# WattMeter_v2.net
KiCad netlist of a schematic drawn in EAGLE
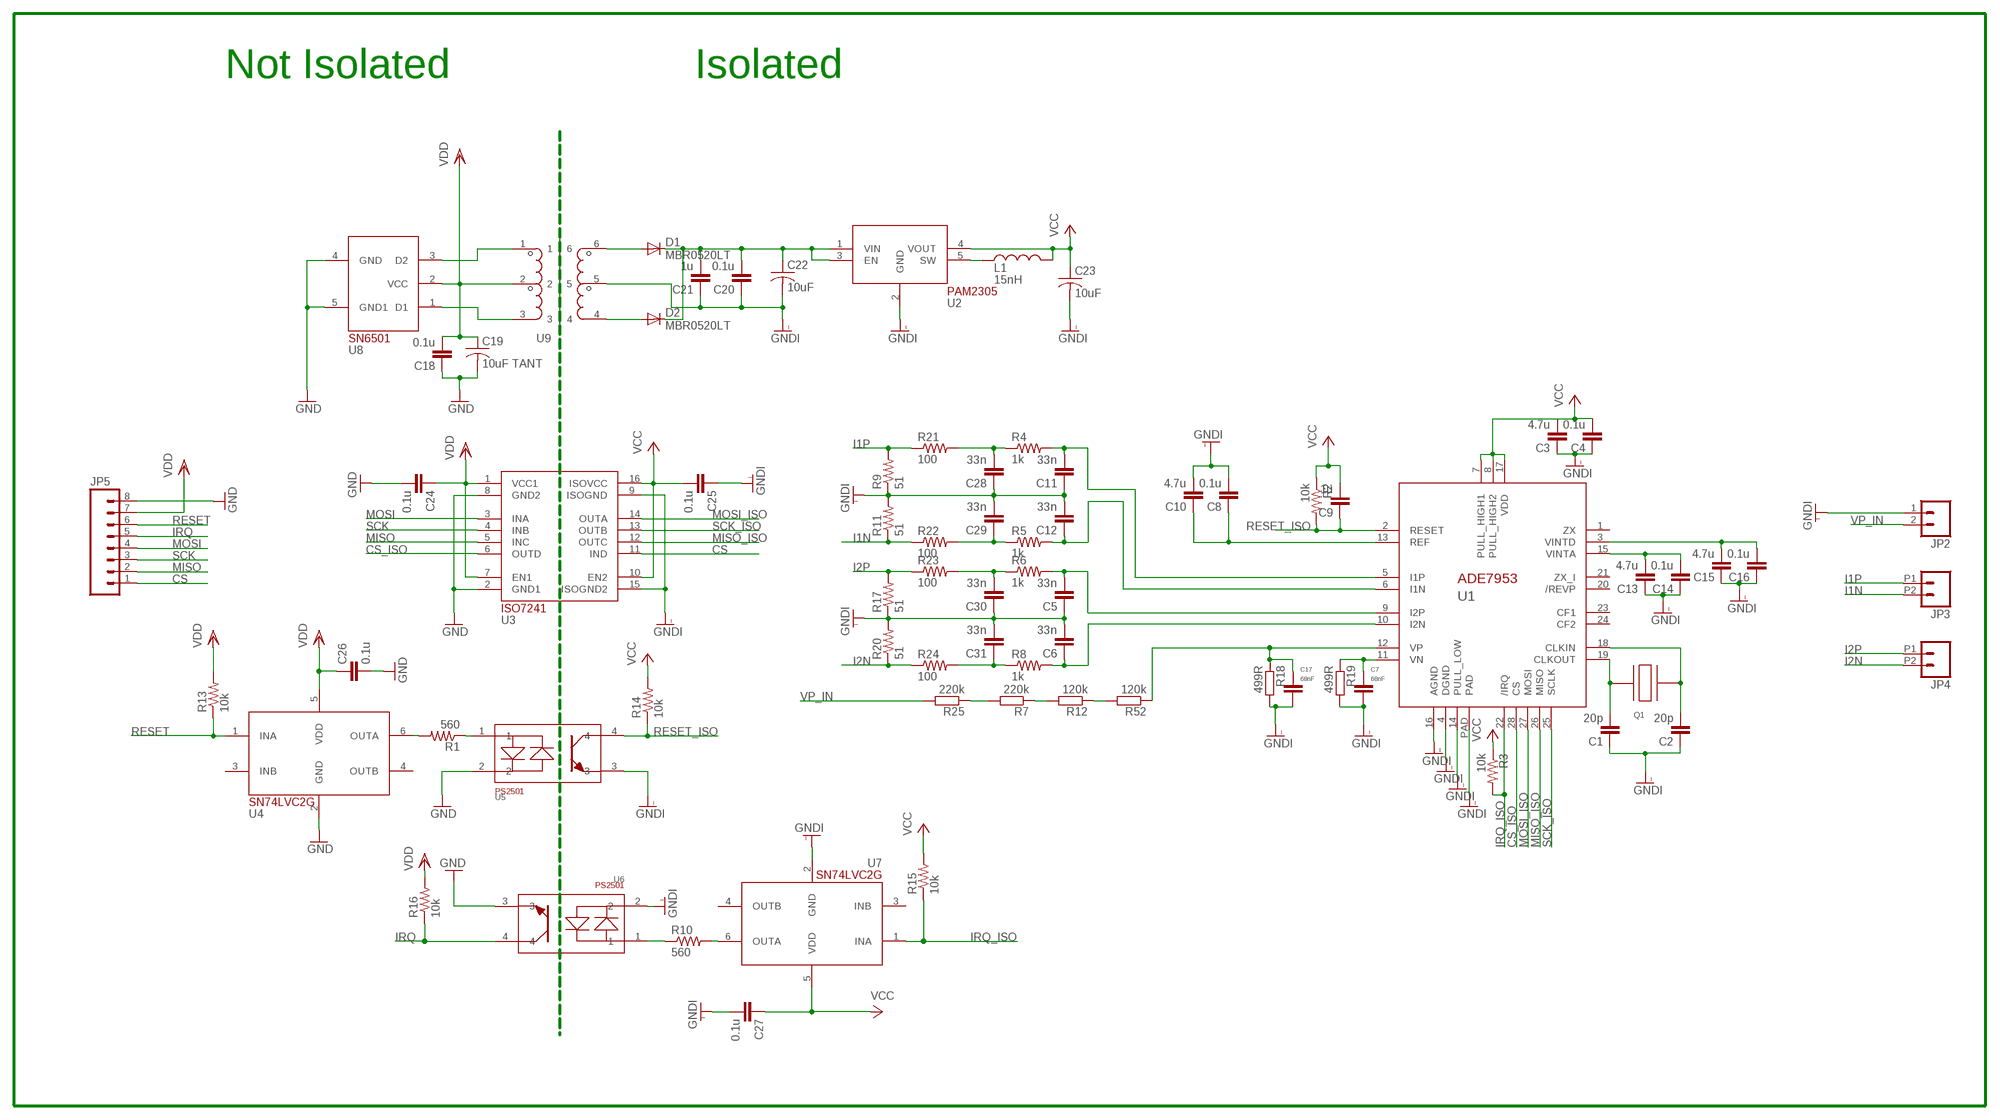
[diagram p0: schematic, sheet 1]

(export (version "E")
  (design (tool "Eeschema 10.0.6"))
  (components
    (comp (ref "C1")
      (value "20p")
      (footprint "eagle-import:0402-CAP")
      (libsource (lib "eagle-import") (part "0402-CAP"))
    )
    (comp (ref "C2")
      (value "20p")
      (footprint "eagle-import:0402-CAP")
      (libsource (lib "eagle-import") (part "0402-CAP"))
    )
    (comp (ref "C3")
      (value "4.7u")
      (footprint "eagle-import:0402-CAP")
      (libsource (lib "eagle-import") (part "0402-CAP"))
    )
    (comp (ref "C4")
      (value "0.1u")
      (footprint "eagle-import:0402-CAP")
      (libsource (lib "eagle-import") (part "0402-CAP"))
    )
    (comp (ref "C5")
      (value "33n")
      (footprint "eagle-import:0402-CAP")
      (libsource (lib "eagle-import") (part "0402-CAP"))
    )
    (comp (ref "C6")
      (value "33n")
      (footprint "eagle-import:0402-CAP")
      (libsource (lib "eagle-import") (part "0402-CAP"))
    )
    (comp (ref "C7")
      (value "68nF")
      (footprint "eagle-import:C0805K")
      (libsource (lib "eagle-import") (part "C-EUC0805K"))
    )
    (comp (ref "C8")
      (value "0.1u")
      (footprint "eagle-import:0402-CAP")
      (libsource (lib "eagle-import") (part "0402-CAP"))
    )
    (comp (ref "C9")
      (value "1u")
      (footprint "eagle-import:0402-CAP")
      (libsource (lib "eagle-import") (part "0402-CAP"))
    )
    (comp (ref "C10")
      (value "4.7u")
      (footprint "eagle-import:0402-CAP")
      (libsource (lib "eagle-import") (part "0402-CAP"))
    )
    (comp (ref "C11")
      (value "33n")
      (footprint "eagle-import:0402-CAP")
      (libsource (lib "eagle-import") (part "0402-CAP"))
    )
    (comp (ref "C12")
      (value "33n")
      (footprint "eagle-import:0402-CAP")
      (libsource (lib "eagle-import") (part "0402-CAP"))
    )
    (comp (ref "C13")
      (value "4.7u")
      (footprint "eagle-import:0402-CAP")
      (libsource (lib "eagle-import") (part "0402-CAP"))
    )
    (comp (ref "C14")
      (value "0.1u")
      (footprint "eagle-import:0402-CAP")
      (libsource (lib "eagle-import") (part "0402-CAP"))
    )
    (comp (ref "C15")
      (value "4.7u")
      (footprint "eagle-import:0402-CAP")
      (libsource (lib "eagle-import") (part "0402-CAP"))
    )
    (comp (ref "C16")
      (value "0.1u")
      (footprint "eagle-import:0402-CAP")
      (libsource (lib "eagle-import") (part "0402-CAP"))
    )
    (comp (ref "C17")
      (value "68nF")
      (footprint "eagle-import:C0805K")
      (libsource (lib "eagle-import") (part "C-EUC0805K"))
    )
    (comp (ref "C18")
      (value "0.1u")
      (footprint "eagle-import:0402-CAP")
      (libsource (lib "eagle-import") (part "0402-CAP"))
    )
    (comp (ref "C19")
      (value "10uF TANT")
      (footprint "eagle-import:C0603")
      (libsource (lib "eagle-import") (part "C-USC0603"))
    )
    (comp (ref "C20")
      (value "0.1u")
      (footprint "eagle-import:0402-CAP")
      (libsource (lib "eagle-import") (part "0402-CAP"))
    )
    (comp (ref "C21")
      (value "1u")
      (footprint "eagle-import:0402-CAP")
      (libsource (lib "eagle-import") (part "0402-CAP"))
    )
    (comp (ref "C22")
      (value "10uF")
      (footprint "eagle-import:C0603")
      (libsource (lib "eagle-import") (part "C-USC0603"))
    )
    (comp (ref "C23")
      (value "10uF")
      (footprint "eagle-import:C0603")
      (libsource (lib "eagle-import") (part "C-USC0603"))
    )
    (comp (ref "C24")
      (value "0.1u")
      (footprint "eagle-import:0402-CAP")
      (libsource (lib "eagle-import") (part "0402-CAP"))
    )
    (comp (ref "C25")
      (value "0.1u")
      (footprint "eagle-import:0402-CAP")
      (libsource (lib "eagle-import") (part "0402-CAP"))
    )
    (comp (ref "C26")
      (value "0.1u")
      (footprint "eagle-import:0402-CAP")
      (libsource (lib "eagle-import") (part "0402-CAP"))
    )
    (comp (ref "C27")
      (value "0.1u")
      (footprint "eagle-import:0402-CAP")
      (libsource (lib "eagle-import") (part "0402-CAP"))
    )
    (comp (ref "C28")
      (value "33n")
      (footprint "eagle-import:0402-CAP")
      (libsource (lib "eagle-import") (part "0402-CAP"))
    )
    (comp (ref "C29")
      (value "33n")
      (footprint "eagle-import:0402-CAP")
      (libsource (lib "eagle-import") (part "0402-CAP"))
    )
    (comp (ref "C30")
      (value "33n")
      (footprint "eagle-import:0402-CAP")
      (libsource (lib "eagle-import") (part "0402-CAP"))
    )
    (comp (ref "C31")
      (value "33n")
      (footprint "eagle-import:0402-CAP")
      (libsource (lib "eagle-import") (part "0402-CAP"))
    )
    (comp (ref "D1")
      (value "MBR0520LT")
      (footprint "eagle-import:SOD123")
      (libsource (lib "eagle-import") (part "MBR0520LT"))
    )
    (comp (ref "D2")
      (value "MBR0520LT")
      (footprint "eagle-import:SOD123")
      (libsource (lib "eagle-import") (part "MBR0520LT"))
    )
    (comp (ref "JP2")
      (value "M025MM")
      (footprint "eagle-import:SCREWTERMINAL-5MM-2")
      (libsource (lib "eagle-import") (part "M025MM"))
    )
    (comp (ref "JP3")
      (value "M022.54MM_SCREWTERM")
      (footprint "eagle-import:1X02_2.54_SCREWTERM")
      (libsource (lib "eagle-import") (part "M022.54MM_SCREWTERM"))
    )
    (comp (ref "JP4")
      (value "M022.54MM_SCREWTERM")
      (footprint "eagle-import:1X02_2.54_SCREWTERM")
      (libsource (lib "eagle-import") (part "M022.54MM_SCREWTERM"))
    )
    (comp (ref "JP5")
      (value "M08")
      (footprint "eagle-import:1X08_ROUND")
      (libsource (lib "eagle-import") (part "M08"))
    )
    (comp (ref "L1")
      (value "15nH")
      (footprint "eagle-import:0402-RES")
      (libsource (lib "eagle-import") (part "IND0402"))
    )
    (comp (ref "Q1")
      (value "QUARTZ_3.58M_2PIN")
      (footprint "eagle-import:HC-49S")
      (libsource (lib "eagle-import") (part "QUARTZ_3.58M_2PIN"))
    )
    (comp (ref "R1")
      (value "560")
      (footprint "eagle-import:0402-RES")
      (libsource (lib "eagle-import") (part "0402-RES"))
    )
    (comp (ref "R2")
      (value "10k")
      (footprint "eagle-import:0402-RES")
      (libsource (lib "eagle-import") (part "0402-RES"))
    )
    (comp (ref "R3")
      (value "10k")
      (footprint "eagle-import:0402-RES")
      (libsource (lib "eagle-import") (part "0402-RES"))
    )
    (comp (ref "R4")
      (value "1k")
      (footprint "eagle-import:0402-RES")
      (libsource (lib "eagle-import") (part "0402-RES"))
    )
    (comp (ref "R5")
      (value "1k")
      (footprint "eagle-import:0402-RES")
      (libsource (lib "eagle-import") (part "0402-RES"))
    )
    (comp (ref "R6")
      (value "1k")
      (footprint "eagle-import:0402-RES")
      (libsource (lib "eagle-import") (part "0402-RES"))
    )
    (comp (ref "R7")
      (value "220k")
      (footprint "eagle-import:R2010")
      (libsource (lib "eagle-import") (part "R-EU_R2010"))
    )
    (comp (ref "R8")
      (value "1k")
      (footprint "eagle-import:0402-RES")
      (libsource (lib "eagle-import") (part "0402-RES"))
    )
    (comp (ref "R9")
      (value "51")
      (footprint "eagle-import:0402-RES")
      (libsource (lib "eagle-import") (part "0402-RES"))
    )
    (comp (ref "R10")
      (value "560")
      (footprint "eagle-import:0402-RES")
      (libsource (lib "eagle-import") (part "0402-RES"))
    )
    (comp (ref "R11")
      (value "51")
      (footprint "eagle-import:0402-RES")
      (libsource (lib "eagle-import") (part "0402-RES"))
    )
    (comp (ref "R12")
      (value "120k")
      (footprint "eagle-import:M1206")
      (libsource (lib "eagle-import") (part "R-EU_M1206"))
    )
    (comp (ref "R13")
      (value "10k")
      (footprint "eagle-import:0402-RES")
      (libsource (lib "eagle-import") (part "0402-RES"))
    )
    (comp (ref "R14")
      (value "10k")
      (footprint "eagle-import:0402-RES")
      (libsource (lib "eagle-import") (part "0402-RES"))
    )
    (comp (ref "R15")
      (value "10k")
      (footprint "eagle-import:0402-RES")
      (libsource (lib "eagle-import") (part "0402-RES"))
    )
    (comp (ref "R16")
      (value "10k")
      (footprint "eagle-import:0402-RES")
      (libsource (lib "eagle-import") (part "0402-RES"))
    )
    (comp (ref "R17")
      (value "51")
      (footprint "eagle-import:0402-RES")
      (libsource (lib "eagle-import") (part "0402-RES"))
    )
    (comp (ref "R18")
      (value "499R")
      (footprint "eagle-import:C0805K@1")
      (libsource (lib "eagle-import") (part "R-EU_"))
    )
    (comp (ref "R19")
      (value "499R")
      (footprint "eagle-import:C0805K@1")
      (libsource (lib "eagle-import") (part "R-EU_"))
    )
    (comp (ref "R20")
      (value "51")
      (footprint "eagle-import:0402-RES")
      (libsource (lib "eagle-import") (part "0402-RES"))
    )
    (comp (ref "R21")
      (value "100")
      (footprint "eagle-import:0402-RES")
      (libsource (lib "eagle-import") (part "0402-RES"))
    )
    (comp (ref "R22")
      (value "100")
      (footprint "eagle-import:0402-RES")
      (libsource (lib "eagle-import") (part "0402-RES"))
    )
    (comp (ref "R23")
      (value "100")
      (footprint "eagle-import:0402-RES")
      (libsource (lib "eagle-import") (part "0402-RES"))
    )
    (comp (ref "R24")
      (value "100")
      (footprint "eagle-import:0402-RES")
      (libsource (lib "eagle-import") (part "0402-RES"))
    )
    (comp (ref "R25")
      (value "220k")
      (footprint "eagle-import:R2010")
      (libsource (lib "eagle-import") (part "R-EU_R2010"))
    )
    (comp (ref "R52")
      (value "120k")
      (footprint "eagle-import:M1206")
      (libsource (lib "eagle-import") (part "R-EU_M1206"))
    )
    (comp (ref "U1")
      (value "ADE7953")
      (footprint "eagle-import:28-WFQFN")
      (libsource (lib "eagle-import") (part "ADE7953"))
    )
    (comp (ref "U2")
      (value "PAM2305")
      (footprint "eagle-import:TSOT25")
      (libsource (lib "eagle-import") (part "PAM2305"))
    )
    (comp (ref "U3")
      (value "ISO7241")
      (footprint "eagle-import:16-SOIC")
      (libsource (lib "eagle-import") (part "ISO7241"))
    )
    (comp (ref "U4")
      (value "SN74LVC")
      (footprint "eagle-import:DCKT")
      (libsource (lib "eagle-import") (part "SN74LVC"))
    )
    (comp (ref "U5")
      (value "PS2505")
      (footprint "eagle-import:4-SMD")
      (libsource (lib "eagle-import") (part "PS2505"))
    )
    (comp (ref "U6")
      (value "PS2505")
      (footprint "eagle-import:4-SMD")
      (libsource (lib "eagle-import") (part "PS2505"))
    )
    (comp (ref "U7")
      (value "SN74LVC")
      (footprint "eagle-import:DCKT")
      (libsource (lib "eagle-import") (part "SN74LVC"))
    )
    (comp (ref "U8")
      (value "SN6501")
      (footprint "eagle-import:SOT-23-5")
      (libsource (lib "eagle-import") (part "SN6501"))
    )
    (comp (ref "U9")
      (value "TRANSFO_3.3")
      (footprint "eagle-import:TRANSFO_3.3")
      (libsource (lib "eagle-import") (part "TRANSFO_3.3"))
    )
  )
  (nets
    (net (code "1") (name "/CS") (class "Default")
      (node (ref "JP5") (pin "1") (pinfunction "1_1") (pintype "passive"))
      (node (ref "U3") (pin "11") (pinfunction "IND_11") (pintype "bidirectional"))
    )
    (net (code "2") (name "/CS_ISO") (class "Default")
      (node (ref "U1") (pin "28") (pinfunction "CS_28") (pintype "bidirectional"))
      (node (ref "U3") (pin "6") (pinfunction "OUTD_6") (pintype "bidirectional"))
    )
    (net (code "3") (name "/I1N") (class "Default")
      (node (ref "JP3") (pin "P2") (pinfunction "2_P2") (pintype "passive"))
      (node (ref "R11") (pin "1") (pinfunction "1_1") (pintype "passive"))
      (node (ref "R22") (pin "1") (pinfunction "1_1") (pintype "passive"))
    )
    (net (code "4") (name "/I1P") (class "Default")
      (node (ref "JP3") (pin "P1") (pinfunction "1_P1") (pintype "passive"))
      (node (ref "R21") (pin "1") (pinfunction "1_1") (pintype "passive"))
      (node (ref "R9") (pin "2") (pinfunction "2_2") (pintype "passive"))
    )
    (net (code "5") (name "/I2N") (class "Default")
      (node (ref "JP4") (pin "P2") (pinfunction "2_P2") (pintype "passive"))
      (node (ref "R20") (pin "1") (pinfunction "1_1") (pintype "passive"))
      (node (ref "R24") (pin "1") (pinfunction "1_1") (pintype "passive"))
    )
    (net (code "6") (name "/I2P") (class "Default")
      (node (ref "JP4") (pin "P1") (pinfunction "1_P1") (pintype "passive"))
      (node (ref "R17") (pin "2") (pinfunction "2_2") (pintype "passive"))
      (node (ref "R23") (pin "1") (pinfunction "1_1") (pintype "passive"))
    )
    (net (code "7") (name "/IRQ") (class "Default")
      (node (ref "JP5") (pin "5") (pinfunction "5_5") (pintype "passive"))
      (node (ref "R16") (pin "1") (pinfunction "1_1") (pintype "passive"))
      (node (ref "U6") (pin "4") (pinfunction "4_4") (pintype "bidirectional"))
    )
    (net (code "8") (name "/IRQ_ISO") (class "Default")
      (node (ref "R15") (pin "1") (pinfunction "1_1") (pintype "passive"))
      (node (ref "R3") (pin "2") (pinfunction "2_2") (pintype "passive"))
      (node (ref "U1") (pin "22") (pinfunction "/IRQ_22") (pintype "bidirectional"))
      (node (ref "U7") (pin "1") (pinfunction "INA_1") (pintype "bidirectional"))
    )
    (net (code "9") (name "/MISO") (class "Default")
      (node (ref "JP5") (pin "2") (pinfunction "2_2") (pintype "passive"))
      (node (ref "U3") (pin "5") (pinfunction "INC_5") (pintype "bidirectional"))
    )
    (net (code "10") (name "/MISO_ISO") (class "Default")
      (node (ref "U1") (pin "26") (pinfunction "MISO_26") (pintype "bidirectional"))
      (node (ref "U3") (pin "12") (pinfunction "OUTC_12") (pintype "bidirectional"))
    )
    (net (code "11") (name "/MOSI") (class "Default")
      (node (ref "JP5") (pin "4") (pinfunction "4_4") (pintype "passive"))
      (node (ref "U3") (pin "3") (pinfunction "INA_3") (pintype "bidirectional"))
    )
    (net (code "12") (name "/MOSI_ISO") (class "Default")
      (node (ref "U1") (pin "27") (pinfunction "MOSI_27") (pintype "bidirectional"))
      (node (ref "U3") (pin "14") (pinfunction "OUTA_14") (pintype "bidirectional"))
    )
    (net (code "13") (name "/RESET") (class "Default")
      (node (ref "JP5") (pin "6") (pinfunction "6_6") (pintype "passive"))
      (node (ref "R13") (pin "1") (pinfunction "1_1") (pintype "passive"))
      (node (ref "U4") (pin "1") (pinfunction "INA_1") (pintype "bidirectional"))
    )
    (net (code "14") (name "/RESET_ISO") (class "Default")
      (node (ref "C9") (pin "1") (pinfunction "1_1") (pintype "passive"))
      (node (ref "R14") (pin "1") (pinfunction "1_1") (pintype "passive"))
      (node (ref "R2") (pin "2") (pinfunction "2_2") (pintype "passive"))
      (node (ref "U1") (pin "2") (pinfunction "RESET_2") (pintype "bidirectional"))
      (node (ref "U5") (pin "4") (pinfunction "4_4") (pintype "bidirectional"))
    )
    (net (code "15") (name "/SCK") (class "Default")
      (node (ref "JP5") (pin "3") (pinfunction "3_3") (pintype "passive"))
      (node (ref "U3") (pin "4") (pinfunction "INB_4") (pintype "bidirectional"))
    )
    (net (code "16") (name "/SCK_ISO") (class "Default")
      (node (ref "U1") (pin "25") (pinfunction "SCLK_25") (pintype "bidirectional"))
      (node (ref "U3") (pin "13") (pinfunction "OUTB_13") (pintype "bidirectional"))
    )
    (net (code "17") (name "/VP_IN") (class "Default")
      (node (ref "JP2") (pin "2") (pinfunction "2_2") (pintype "passive"))
      (node (ref "R25") (pin "2") (pinfunction "2_2") (pintype "passive"))
    )
    (net (code "18") (name "GND") (class "Default")
      (node (ref "C18") (pin "1") (pinfunction "1_1") (pintype "passive"))
      (node (ref "C19") (pin "2") (pinfunction "2_2") (pintype "passive"))
      (node (ref "C24") (pin "2") (pinfunction "2_2") (pintype "passive"))
      (node (ref "C26") (pin "2") (pinfunction "2_2") (pintype "passive"))
      (node (ref "JP5") (pin "8") (pinfunction "8_8") (pintype "passive"))
      (node (ref "U3") (pin "2") (pinfunction "GND1_2") (pintype "bidirectional"))
      (node (ref "U3") (pin "8") (pinfunction "GND2_8") (pintype "bidirectional"))
      (node (ref "U4") (pin "2") (pinfunction "GND_2") (pintype "bidirectional"))
      (node (ref "U5") (pin "2") (pinfunction "2_2") (pintype "bidirectional"))
      (node (ref "U6") (pin "3") (pinfunction "3_3") (pintype "bidirectional"))
      (node (ref "U8") (pin "4") (pinfunction "GND_4") (pintype "bidirectional"))
      (node (ref "U8") (pin "5") (pinfunction "GND1_5") (pintype "bidirectional"))
    )
    (net (code "19") (name "GNDI") (class "Default")
      (node (ref "C1") (pin "1") (pinfunction "1_1") (pintype "passive"))
      (node (ref "C10") (pin "2") (pinfunction "2_2") (pintype "passive"))
      (node (ref "C11") (pin "1") (pinfunction "1_1") (pintype "passive"))
      (node (ref "C12") (pin "2") (pinfunction "2_2") (pintype "passive"))
      (node (ref "C13") (pin "1") (pinfunction "1_1") (pintype "passive"))
      (node (ref "C14") (pin "1") (pinfunction "1_1") (pintype "passive"))
      (node (ref "C15") (pin "1") (pinfunction "1_1") (pintype "passive"))
      (node (ref "C16") (pin "1") (pinfunction "1_1") (pintype "passive"))
      (node (ref "C17") (pin "2") (pinfunction "2_2") (pintype "passive"))
      (node (ref "C2") (pin "1") (pinfunction "1_1") (pintype "passive"))
      (node (ref "C20") (pin "1") (pinfunction "1_1") (pintype "passive"))
      (node (ref "C21") (pin "1") (pinfunction "1_1") (pintype "passive"))
      (node (ref "C22") (pin "2") (pinfunction "2_2") (pintype "passive"))
      (node (ref "C23") (pin "2") (pinfunction "2_2") (pintype "passive"))
      (node (ref "C25") (pin "1") (pinfunction "1_1") (pintype "passive"))
      (node (ref "C27") (pin "2") (pinfunction "2_2") (pintype "passive"))
      (node (ref "C28") (pin "1") (pinfunction "1_1") (pintype "passive"))
      (node (ref "C29") (pin "2") (pinfunction "2_2") (pintype "passive"))
      (node (ref "C3") (pin "1") (pinfunction "1_1") (pintype "passive"))
      (node (ref "C30") (pin "1") (pinfunction "1_1") (pintype "passive"))
      (node (ref "C31") (pin "2") (pinfunction "2_2") (pintype "passive"))
      (node (ref "C4") (pin "1") (pinfunction "1_1") (pintype "passive"))
      (node (ref "C5") (pin "1") (pinfunction "1_1") (pintype "passive"))
      (node (ref "C6") (pin "2") (pinfunction "2_2") (pintype "passive"))
      (node (ref "C7") (pin "2") (pinfunction "2_2") (pintype "passive"))
      (node (ref "C8") (pin "2") (pinfunction "2_2") (pintype "passive"))
      (node (ref "JP2") (pin "1") (pinfunction "1_1") (pintype "passive"))
      (node (ref "R11") (pin "2") (pinfunction "2_2") (pintype "passive"))
      (node (ref "R17") (pin "1") (pinfunction "1_1") (pintype "passive"))
      (node (ref "R18") (pin "2") (pinfunction "2_2") (pintype "passive"))
      (node (ref "R19") (pin "2") (pinfunction "2_2") (pintype "passive"))
      (node (ref "R20") (pin "2") (pinfunction "2_2") (pintype "passive"))
      (node (ref "R9") (pin "1") (pinfunction "1_1") (pintype "passive"))
      (node (ref "U1") (pin "14") (pinfunction "PULL_LOW_14") (pintype "bidirectional"))
      (node (ref "U1") (pin "16") (pinfunction "AGND_16") (pintype "bidirectional"))
      (node (ref "U1") (pin "4") (pinfunction "DGND_4") (pintype "bidirectional"))
      (node (ref "U1") (pin "PAD") (pinfunction "PAD_PAD") (pintype "bidirectional"))
      (node (ref "U2") (pin "2") (pinfunction "GND_2") (pintype "bidirectional"))
      (node (ref "U3") (pin "15") (pinfunction "ISOGND2_15") (pintype "bidirectional"))
      (node (ref "U3") (pin "9") (pinfunction "ISOGND_9") (pintype "bidirectional"))
      (node (ref "U5") (pin "3") (pinfunction "3_3") (pintype "bidirectional"))
      (node (ref "U6") (pin "2") (pinfunction "2_2") (pintype "bidirectional"))
      (node (ref "U7") (pin "2") (pinfunction "GND_2") (pintype "bidirectional"))
      (node (ref "U9") (pin "5") (pinfunction "5_5") (pintype "bidirectional"))
    )
    (net (code "20") (name "Net-(C28-Pad2)") (class "Default")
      (node (ref "C28") (pin "2") (pinfunction "2_2") (pintype "passive"))
      (node (ref "R21") (pin "2") (pinfunction "2_2") (pintype "passive"))
      (node (ref "R4") (pin "1") (pinfunction "1_1") (pintype "passive"))
    )
    (net (code "21") (name "Net-(C29-Pad1)") (class "Default")
      (node (ref "C29") (pin "1") (pinfunction "1_1") (pintype "passive"))
      (node (ref "R22") (pin "2") (pinfunction "2_2") (pintype "passive"))
      (node (ref "R5") (pin "1") (pinfunction "1_1") (pintype "passive"))
    )
    (net (code "22") (name "Net-(C30-Pad2)") (class "Default")
      (node (ref "C30") (pin "2") (pinfunction "2_2") (pintype "passive"))
      (node (ref "R23") (pin "2") (pinfunction "2_2") (pintype "passive"))
      (node (ref "R6") (pin "1") (pinfunction "1_1") (pintype "passive"))
    )
    (net (code "23") (name "Net-(C31-Pad1)") (class "Default")
      (node (ref "C31") (pin "1") (pinfunction "1_1") (pintype "passive"))
      (node (ref "R24") (pin "2") (pinfunction "2_2") (pintype "passive"))
      (node (ref "R8") (pin "1") (pinfunction "1_1") (pintype "passive"))
    )
    (net (code "24") (name "Net-(D1-PadA)") (class "Default")
      (node (ref "D1") (pin "A") (pinfunction "A_A") (pintype "passive"))
      (node (ref "U9") (pin "6") (pinfunction "6_6") (pintype "bidirectional"))
    )
    (net (code "25") (name "Net-(D2-PadA)") (class "Default")
      (node (ref "D2") (pin "A") (pinfunction "A_A") (pintype "passive"))
      (node (ref "U9") (pin "4") (pinfunction "4_4") (pintype "bidirectional"))
    )
    (net (code "26") (name "Net-(R1-Pad1)") (class "Default")
      (node (ref "R1") (pin "1") (pinfunction "1_1") (pintype "passive"))
      (node (ref "U5") (pin "1") (pinfunction "1_1") (pintype "bidirectional"))
    )
    (net (code "27") (name "Net-(R10-Pad1)") (class "Default")
      (node (ref "R10") (pin "1") (pinfunction "1_1") (pintype "passive"))
      (node (ref "U6") (pin "1") (pinfunction "1_1") (pintype "bidirectional"))
    )
    (net (code "28") (name "Net-(R12-Pad1)") (class "Default")
      (node (ref "R12") (pin "1") (pinfunction "1_1") (pintype "passive"))
      (node (ref "R52") (pin "2") (pinfunction "2_2") (pintype "passive"))
    )
    (net (code "29") (name "Net-(R12-Pad2)") (class "Default")
      (node (ref "R12") (pin "2") (pinfunction "2_2") (pintype "passive"))
      (node (ref "R7") (pin "1") (pinfunction "1_1") (pintype "passive"))
    )
    (net (code "30") (name "Net-(R25-Pad1)") (class "Default")
      (node (ref "R25") (pin "1") (pinfunction "1_1") (pintype "passive"))
      (node (ref "R7") (pin "2") (pinfunction "2_2") (pintype "passive"))
    )
    (net (code "31") (name "Net-(U1-CLKIN)") (class "Default")
      (node (ref "C2") (pin "2") (pinfunction "2_2") (pintype "passive"))
      (node (ref "Q1") (pin "2") (pinfunction "2_2") (pintype "bidirectional"))
      (node (ref "U1") (pin "18") (pinfunction "CLKIN_18") (pintype "bidirectional"))
    )
    (net (code "32") (name "Net-(U1-CLKOUT)") (class "Default")
      (node (ref "C1") (pin "2") (pinfunction "2_2") (pintype "passive"))
      (node (ref "Q1") (pin "1") (pinfunction "1_1") (pintype "bidirectional"))
      (node (ref "U1") (pin "19") (pinfunction "CLKOUT_19") (pintype "bidirectional"))
    )
    (net (code "33") (name "Net-(U1-I1N)") (class "Default")
      (node (ref "C12") (pin "1") (pinfunction "1_1") (pintype "passive"))
      (node (ref "R5") (pin "2") (pinfunction "2_2") (pintype "passive"))
      (node (ref "U1") (pin "6") (pinfunction "I1N_6") (pintype "bidirectional"))
    )
    (net (code "34") (name "Net-(U1-I1P)") (class "Default")
      (node (ref "C11") (pin "2") (pinfunction "2_2") (pintype "passive"))
      (node (ref "R4") (pin "2") (pinfunction "2_2") (pintype "passive"))
      (node (ref "U1") (pin "5") (pinfunction "I1P_5") (pintype "bidirectional"))
    )
    (net (code "35") (name "Net-(U1-I2N)") (class "Default")
      (node (ref "C6") (pin "1") (pinfunction "1_1") (pintype "passive"))
      (node (ref "R8") (pin "2") (pinfunction "2_2") (pintype "passive"))
      (node (ref "U1") (pin "10") (pinfunction "I2N_10") (pintype "bidirectional"))
    )
    (net (code "36") (name "Net-(U1-I2P)") (class "Default")
      (node (ref "C5") (pin "2") (pinfunction "2_2") (pintype "passive"))
      (node (ref "R6") (pin "2") (pinfunction "2_2") (pintype "passive"))
      (node (ref "U1") (pin "9") (pinfunction "I2P_9") (pintype "bidirectional"))
    )
    (net (code "37") (name "Net-(U1-REF)") (class "Default")
      (node (ref "C10") (pin "1") (pinfunction "1_1") (pintype "passive"))
      (node (ref "C8") (pin "1") (pinfunction "1_1") (pintype "passive"))
      (node (ref "U1") (pin "13") (pinfunction "REF_13") (pintype "bidirectional"))
    )
    (net (code "38") (name "Net-(U1-VINTA)") (class "Default")
      (node (ref "C13") (pin "2") (pinfunction "2_2") (pintype "passive"))
      (node (ref "C14") (pin "2") (pinfunction "2_2") (pintype "passive"))
      (node (ref "U1") (pin "15") (pinfunction "VINTA_15") (pintype "bidirectional"))
    )
    (net (code "39") (name "Net-(U1-VINTD)") (class "Default")
      (node (ref "C15") (pin "2") (pinfunction "2_2") (pintype "passive"))
      (node (ref "C16") (pin "2") (pinfunction "2_2") (pintype "passive"))
      (node (ref "U1") (pin "3") (pinfunction "VINTD_3") (pintype "bidirectional"))
    )
    (net (code "40") (name "Net-(U1-VN)") (class "Default")
      (node (ref "C7") (pin "1") (pinfunction "1_1") (pintype "passive"))
      (node (ref "R19") (pin "1") (pinfunction "1_1") (pintype "passive"))
      (node (ref "U1") (pin "11") (pinfunction "VN_11") (pintype "bidirectional"))
    )
    (net (code "41") (name "Net-(U1-VP)") (class "Default")
      (node (ref "C17") (pin "1") (pinfunction "1_1") (pintype "passive"))
      (node (ref "R18") (pin "1") (pinfunction "1_1") (pintype "passive"))
      (node (ref "R52") (pin "1") (pinfunction "1_1") (pintype "passive"))
      (node (ref "U1") (pin "12") (pinfunction "VP_12") (pintype "bidirectional"))
    )
    (net (code "42") (name "Net-(U2-EN)") (class "Default")
      (node (ref "C20") (pin "2") (pinfunction "2_2") (pintype "passive"))
      (node (ref "C21") (pin "2") (pinfunction "2_2") (pintype "passive"))
      (node (ref "C22") (pin "1") (pinfunction "1_1") (pintype "passive"))
      (node (ref "D1") (pin "C") (pinfunction "C_C") (pintype "passive"))
      (node (ref "D2") (pin "C") (pinfunction "C_C") (pintype "passive"))
      (node (ref "U2") (pin "1") (pinfunction "VIN_1") (pintype "bidirectional"))
      (node (ref "U2") (pin "3") (pinfunction "EN_3") (pintype "bidirectional"))
    )
    (net (code "43") (name "Net-(U2-SW)") (class "Default")
      (node (ref "L1") (pin "1") (pinfunction "1_1") (pintype "bidirectional"))
      (node (ref "U2") (pin "5") (pinfunction "SW_5") (pintype "bidirectional"))
    )
    (net (code "44") (name "Net-(U4-OUTA)") (class "Default")
      (node (ref "R1") (pin "2") (pinfunction "2_2") (pintype "passive"))
      (node (ref "U4") (pin "6") (pinfunction "OUTA_6") (pintype "bidirectional"))
    )
    (net (code "45") (name "Net-(U7-OUTA)") (class "Default")
      (node (ref "R10") (pin "2") (pinfunction "2_2") (pintype "passive"))
      (node (ref "U7") (pin "6") (pinfunction "OUTA_6") (pintype "bidirectional"))
    )
    (net (code "46") (name "Net-(U8-D1)") (class "Default")
      (node (ref "U8") (pin "1") (pinfunction "D1_1") (pintype "bidirectional"))
      (node (ref "U9") (pin "3") (pinfunction "3_3") (pintype "bidirectional"))
    )
    (net (code "47") (name "Net-(U8-D2)") (class "Default")
      (node (ref "U8") (pin "3") (pinfunction "D2_3") (pintype "bidirectional"))
      (node (ref "U9") (pin "1") (pinfunction "1_1") (pintype "bidirectional"))
    )
    (net (code "48") (name "VCC") (class "Default")
      (node (ref "C23") (pin "1") (pinfunction "1_1") (pintype "passive"))
      (node (ref "C25") (pin "2") (pinfunction "2_2") (pintype "passive"))
      (node (ref "C27") (pin "1") (pinfunction "1_1") (pintype "passive"))
      (node (ref "C3") (pin "2") (pinfunction "2_2") (pintype "passive"))
      (node (ref "C4") (pin "2") (pinfunction "2_2") (pintype "passive"))
      (node (ref "C9") (pin "2") (pinfunction "2_2") (pintype "passive"))
      (node (ref "L1") (pin "2") (pinfunction "2_2") (pintype "bidirectional"))
      (node (ref "R14") (pin "2") (pinfunction "2_2") (pintype "passive"))
      (node (ref "R15") (pin "2") (pinfunction "2_2") (pintype "passive"))
      (node (ref "R2") (pin "1") (pinfunction "1_1") (pintype "passive"))
      (node (ref "R3") (pin "1") (pinfunction "1_1") (pintype "passive"))
      (node (ref "U1") (pin "17") (pinfunction "VDD_17") (pintype "bidirectional"))
      (node (ref "U1") (pin "7") (pinfunction "PULL_HIGH1_7") (pintype "bidirectional"))
      (node (ref "U1") (pin "8") (pinfunction "PULL_HIGH2_8") (pintype "bidirectional"))
      (node (ref "U2") (pin "4") (pinfunction "VOUT_4") (pintype "bidirectional"))
      (node (ref "U3") (pin "10") (pinfunction "EN2_10") (pintype "bidirectional"))
      (node (ref "U3") (pin "16") (pinfunction "ISOVCC_16") (pintype "bidirectional"))
      (node (ref "U7") (pin "5") (pinfunction "VDD_5") (pintype "bidirectional"))
    )
    (net (code "49") (name "VDD") (class "Default")
      (node (ref "C18") (pin "2") (pinfunction "2_2") (pintype "passive"))
      (node (ref "C19") (pin "1") (pinfunction "1_1") (pintype "passive"))
      (node (ref "C24") (pin "1") (pinfunction "1_1") (pintype "passive"))
      (node (ref "C26") (pin "1") (pinfunction "1_1") (pintype "passive"))
      (node (ref "JP5") (pin "7") (pinfunction "7_7") (pintype "passive"))
      (node (ref "R13") (pin "2") (pinfunction "2_2") (pintype "passive"))
      (node (ref "R16") (pin "2") (pinfunction "2_2") (pintype "passive"))
      (node (ref "U3") (pin "1") (pinfunction "VCC1_1") (pintype "bidirectional"))
      (node (ref "U3") (pin "7") (pinfunction "EN1_7") (pintype "bidirectional"))
      (node (ref "U4") (pin "5") (pinfunction "VDD_5") (pintype "bidirectional"))
      (node (ref "U8") (pin "2") (pinfunction "VCC_2") (pintype "bidirectional"))
      (node (ref "U9") (pin "2") (pinfunction "2_2") (pintype "bidirectional"))
    )
    (net (code "50") (name "unconnected-(U1-CF1-Pad23)") (class "Default")
      (node (ref "U1") (pin "23") (pinfunction "CF1_23") (pintype "bidirectional"))
    )
    (net (code "51") (name "unconnected-(U1-CF2-Pad24)") (class "Default")
      (node (ref "U1") (pin "24") (pinfunction "CF2_24") (pintype "bidirectional"))
    )
    (net (code "52") (name "unconnected-(U1-ZX-Pad1)") (class "Default")
      (node (ref "U1") (pin "1") (pinfunction "ZX_1") (pintype "bidirectional"))
    )
    (net (code "53") (name "unconnected-(U1-ZX_I-Pad21)") (class "Default")
      (node (ref "U1") (pin "21") (pinfunction "ZX_I_21") (pintype "bidirectional"))
    )
    (net (code "54") (name "unconnected-(U1-{slash}REVP-Pad20)") (class "Default")
      (node (ref "U1") (pin "20") (pinfunction "/REVP_20") (pintype "bidirectional"))
    )
    (net (code "55") (name "unconnected-(U4-INB-Pad3)") (class "Default")
      (node (ref "U4") (pin "3") (pinfunction "INB_3") (pintype "bidirectional"))
    )
    (net (code "56") (name "unconnected-(U4-OUTB-Pad4)") (class "Default")
      (node (ref "U4") (pin "4") (pinfunction "OUTB_4") (pintype "bidirectional"))
    )
    (net (code "57") (name "unconnected-(U7-INB-Pad3)") (class "Default")
      (node (ref "U7") (pin "3") (pinfunction "INB_3") (pintype "bidirectional"))
    )
    (net (code "58") (name "unconnected-(U7-OUTB-Pad4)") (class "Default")
      (node (ref "U7") (pin "4") (pinfunction "OUTB_4") (pintype "bidirectional"))
    )
  )
)
